# controller_rev1_1_flat.net
KiCad netlist of a schematic drawn in EAGLE
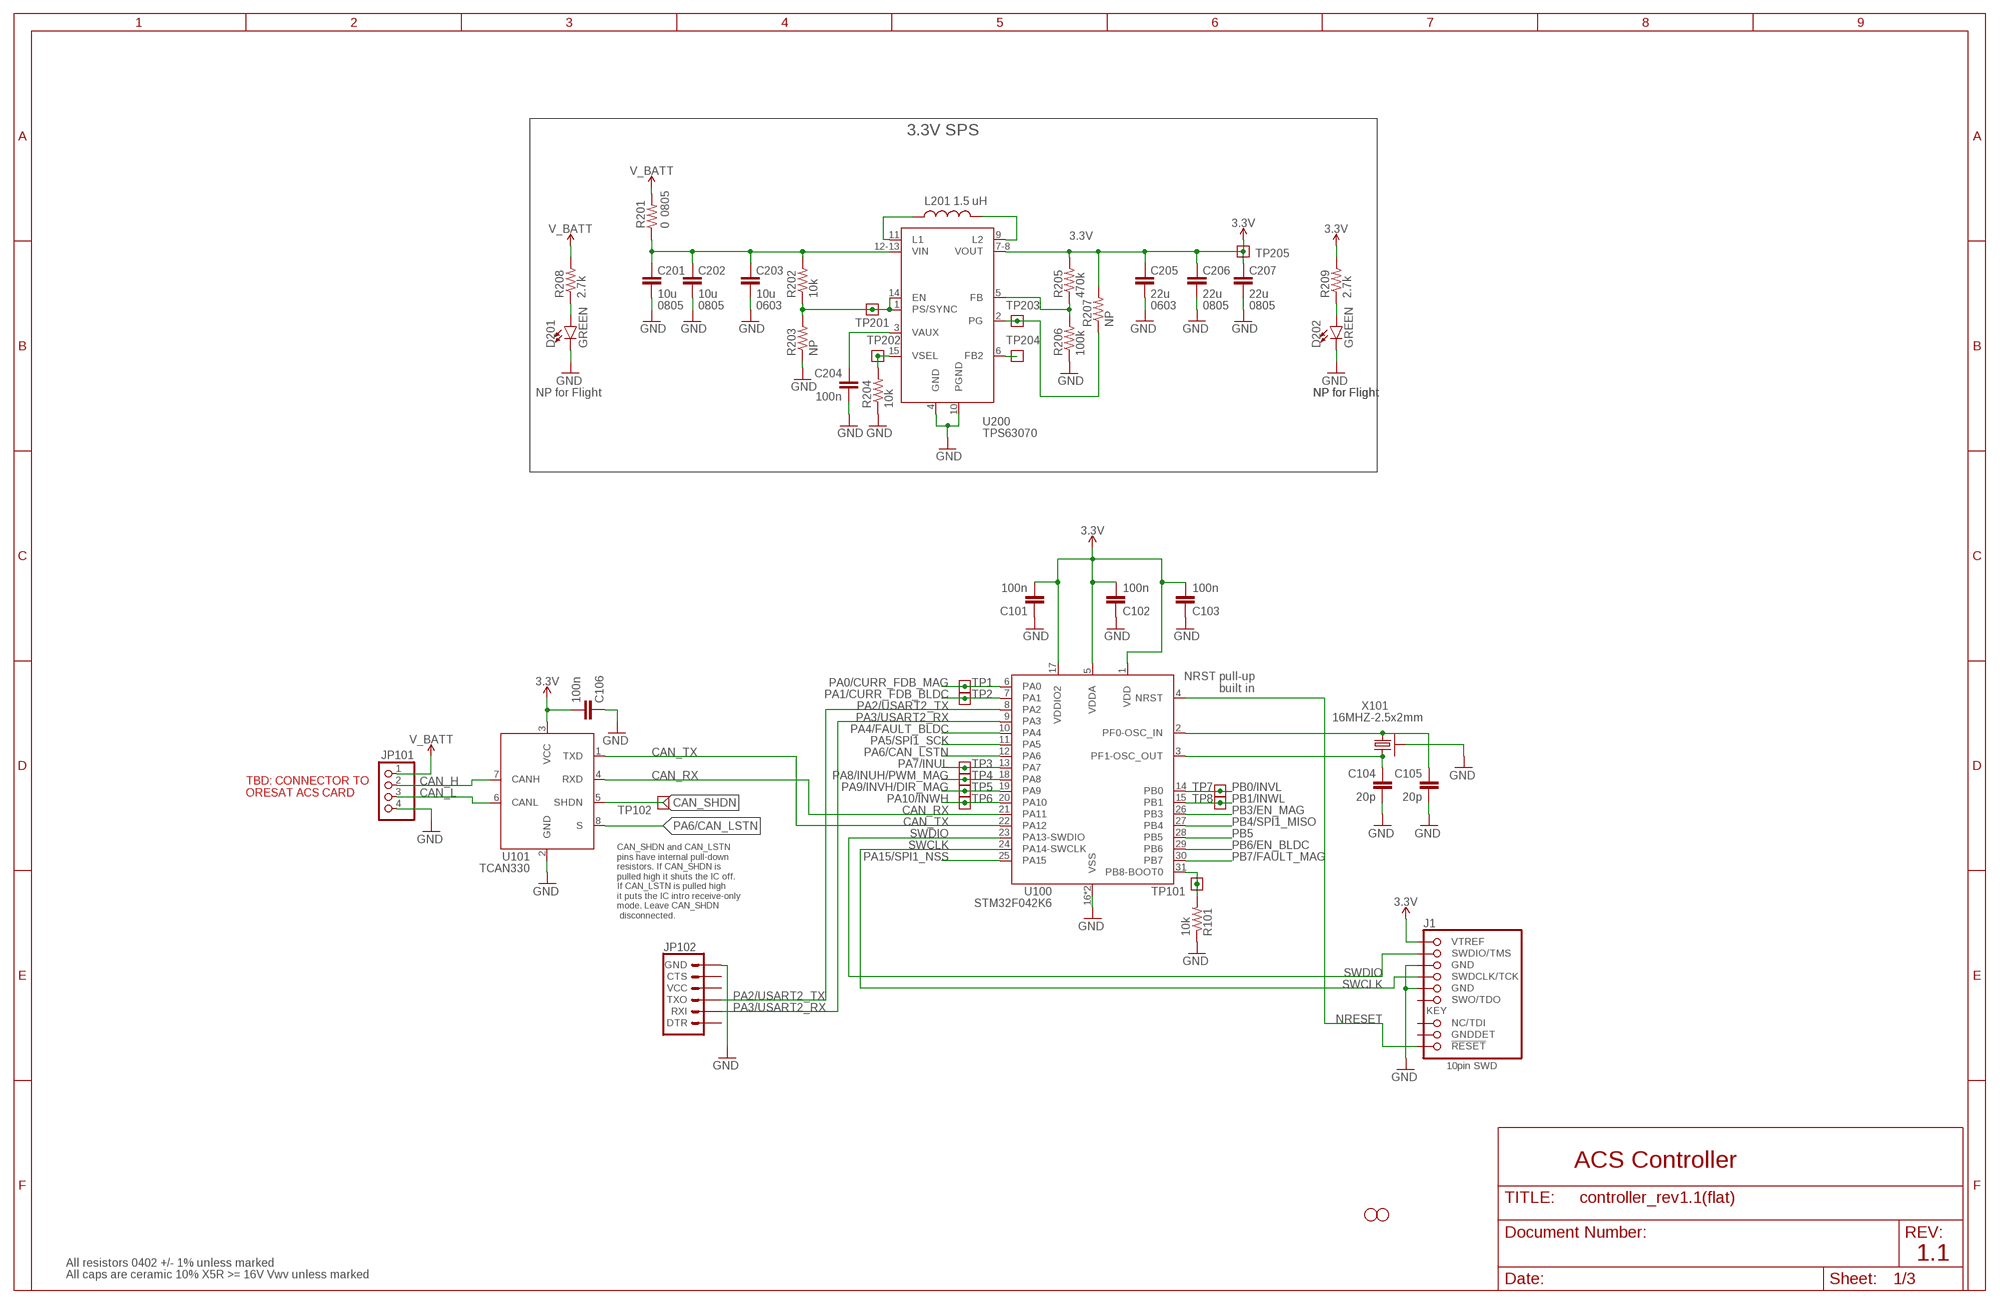
[diagram p0: schematic, sheet 1]
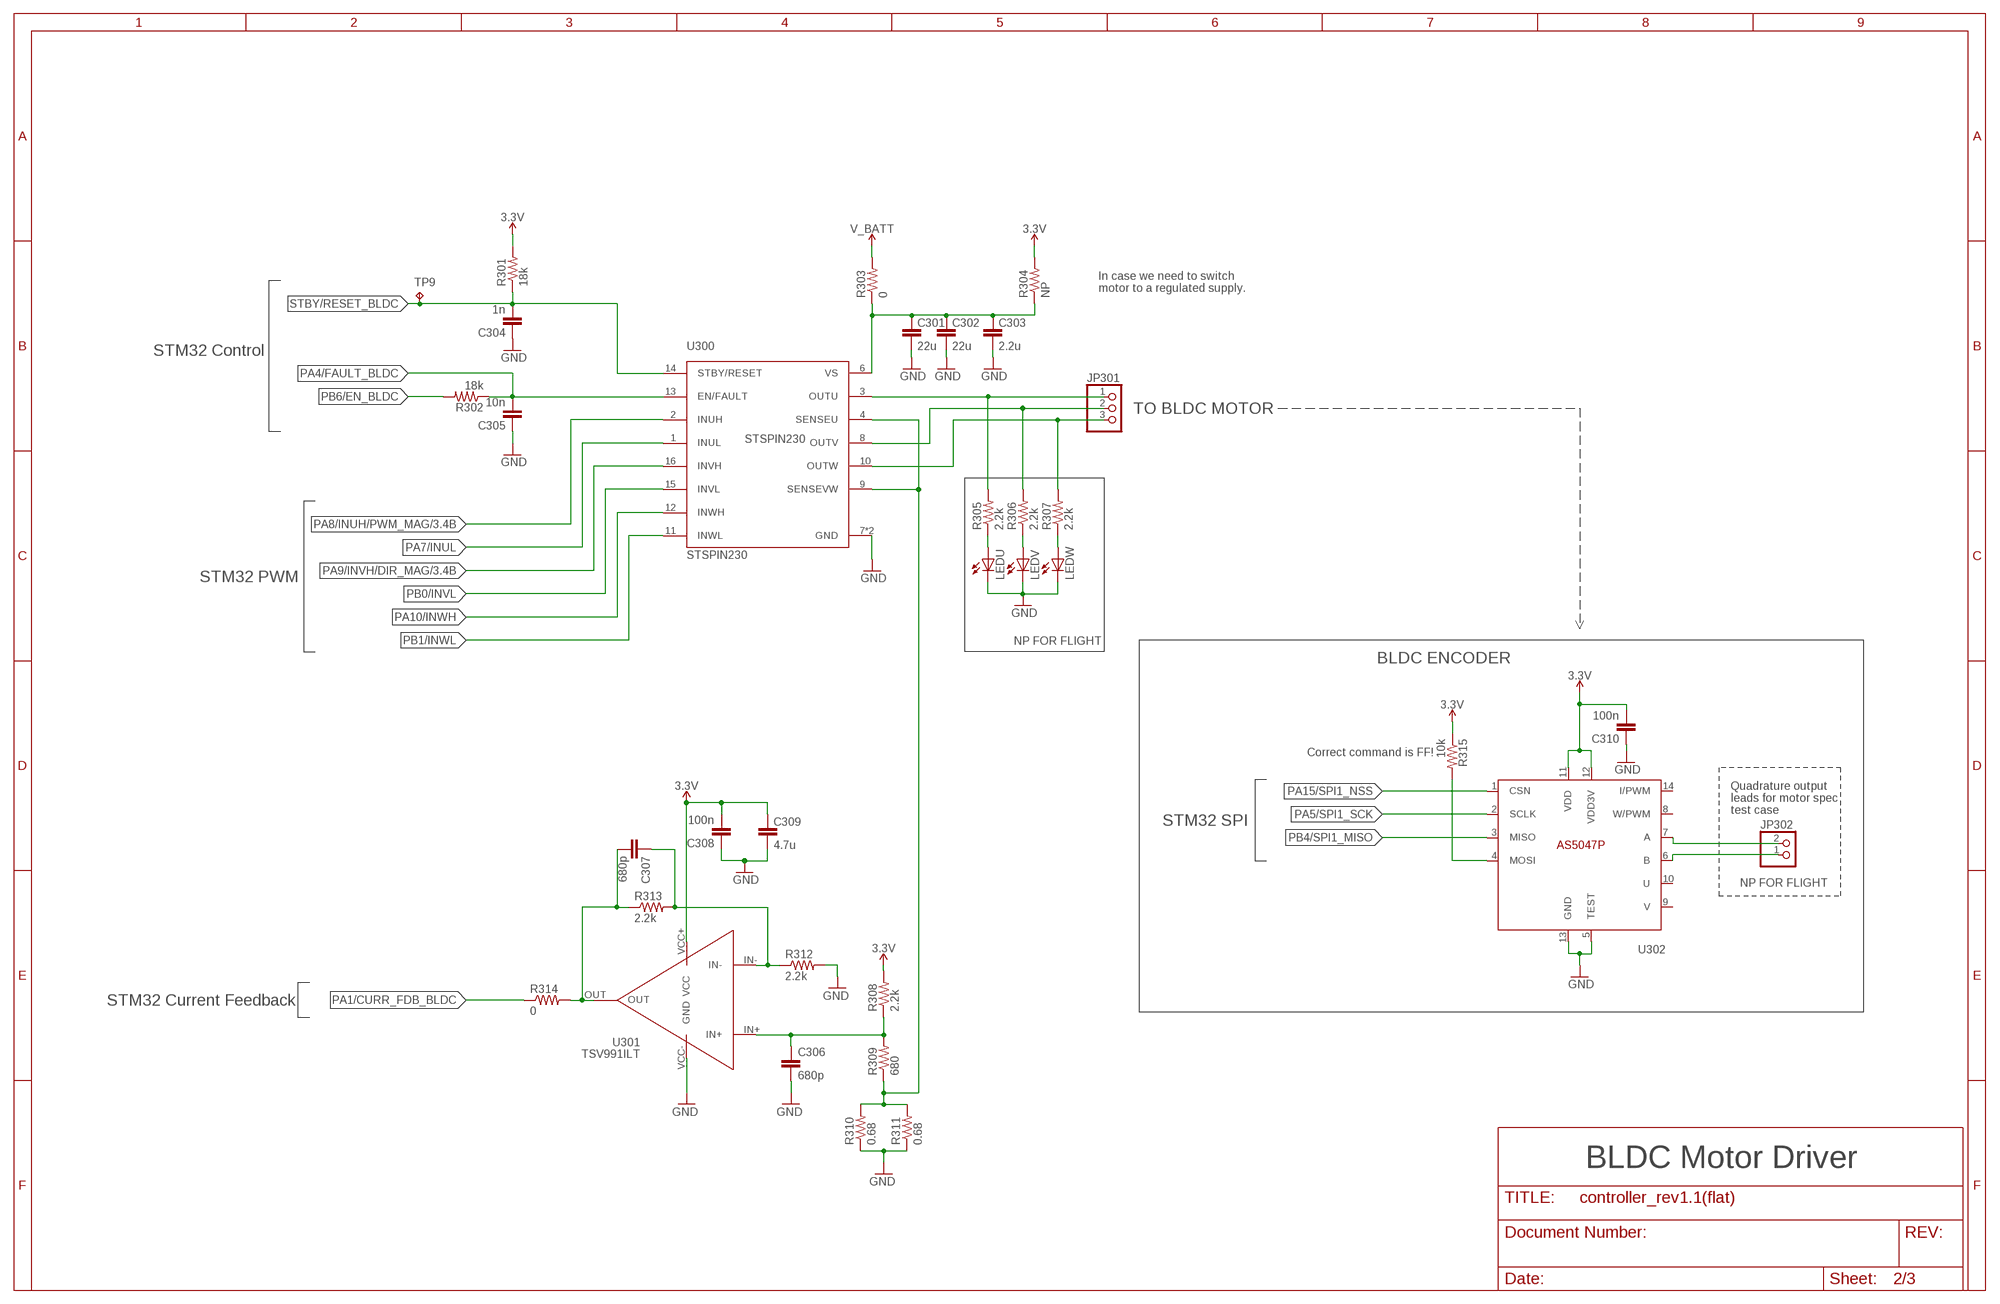
[diagram p1: schematic, sheet 2]
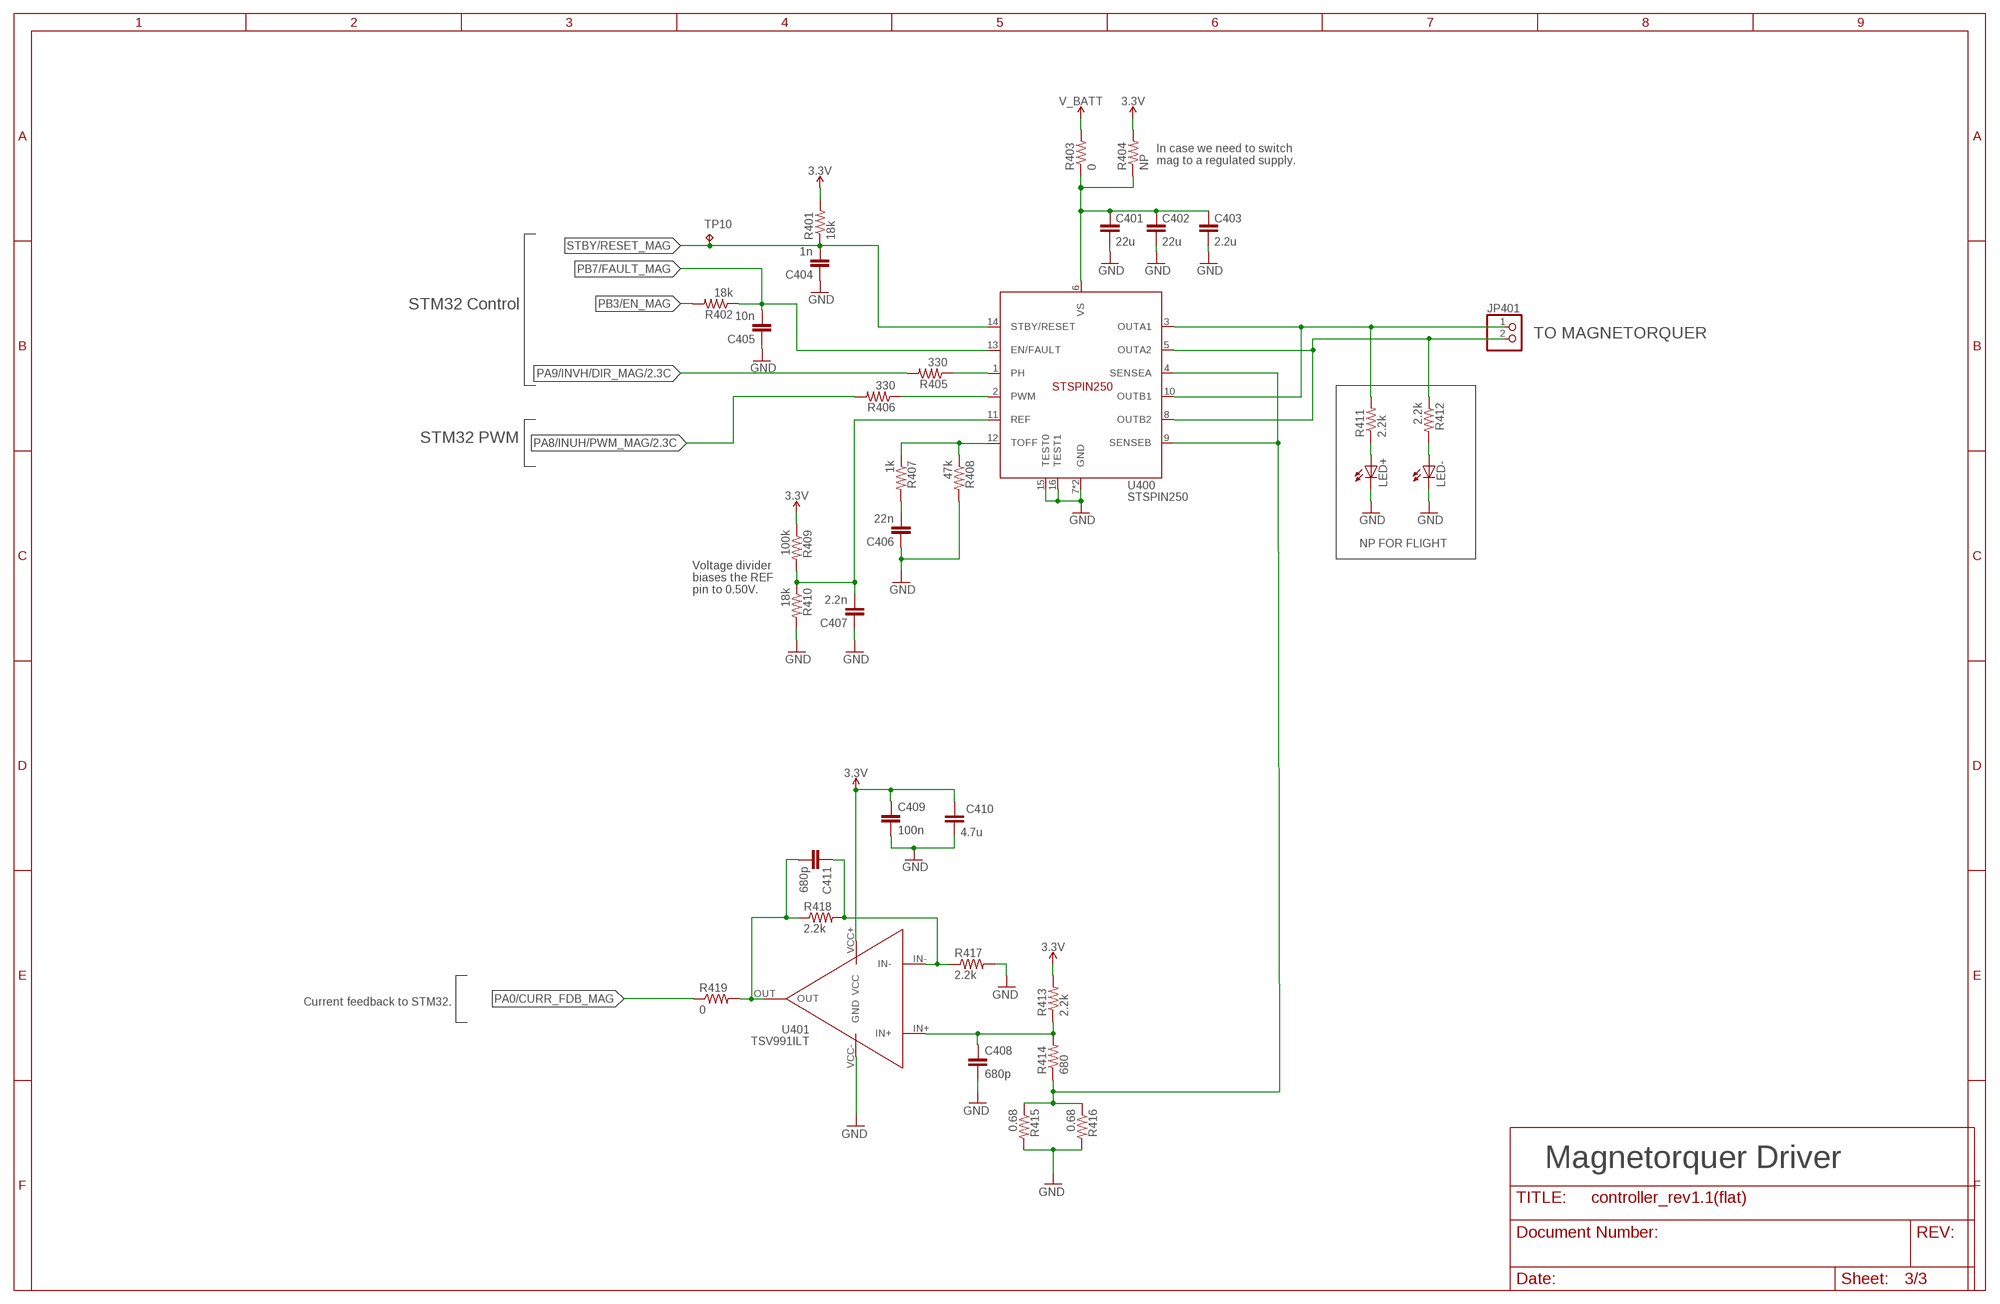
[diagram p2: schematic, sheet 3]

(export (version "E")
  (design (tool "Eeschema 10.0.6"))
  (components
    (comp (ref "C401")
      (value "22u")
      (footprint "eagle-import:.0603-B-NOSILK")
      (fields (field (name "MFR") "Samsung") (field (name "MPN") "CL05B104KO5NNNC"))
      (libsource (lib "eagle-import") (part "C-EU0603-B-NOSILK"))
    )
    (comp (ref "C402")
      (value "22u")
      (footprint "eagle-import:.0603-B-NOSILK")
      (fields (field (name "MFR") "Samsung") (field (name "MPN") "CL05B104KO5NNNC"))
      (libsource (lib "eagle-import") (part "C-EU0603-B-NOSILK"))
    )
    (comp (ref "C403")
      (value "2.2u")
      (footprint "eagle-import:.0603-B-NOSILK")
      (fields (field (name "MFR") "Samsung") (field (name "MPN") "CL05B104KO5NNNC"))
      (libsource (lib "eagle-import") (part "C-EU0603-B-NOSILK"))
    )
    (comp (ref "C404")
      (value "1n")
      (footprint "eagle-import:.0402-B-NOSILK")
      (fields (field (name "MFR") "Samsung") (field (name "MPN") "CL05B104KO5NNNC"))
      (libsource (lib "eagle-import") (part "rcl_custom_C-EU0402-B-NOSILK"))
    )
    (comp (ref "C405")
      (value "10n")
      (footprint "eagle-import:.0402-B-NOSILK")
      (fields (field (name "MFR") "Samsung") (field (name "MPN") "CL05B104KO5NNNC"))
      (libsource (lib "eagle-import") (part "rcl_custom_C-EU0402-B-NOSILK"))
    )
    (comp (ref "C406")
      (value "22n")
      (footprint "eagle-import:.0402-B-NOSILK")
      (fields (field (name "MFR") "Samsung") (field (name "MPN") "CL05B104KO5NNNC"))
      (libsource (lib "eagle-import") (part "rcl_custom_C-EU0402-B-NOSILK"))
    )
    (comp (ref "C407")
      (value "2.2n")
      (footprint "eagle-import:.0402-B-NOSILK")
      (fields (field (name "MFR") "Samsung") (field (name "MPN") "CL05B104KO5NNNC"))
      (libsource (lib "eagle-import") (part "rcl_custom_C-EU0402-B-NOSILK"))
    )
    (comp (ref "C408")
      (value "680p")
      (footprint "eagle-import:.0402-B-NOSILK")
      (fields (field (name "MFR") "Samsung") (field (name "MPN") "CL05B104KO5NNNC"))
      (libsource (lib "eagle-import") (part "rcl_custom_C-EU0402-B-NOSILK"))
    )
    (comp (ref "C409")
      (value "100n")
      (footprint "eagle-import:.0402-B-NOSILK")
      (fields (field (name "MFR") "Samsung") (field (name "MPN") "CL05B104KO5NNNC"))
      (libsource (lib "eagle-import") (part "rcl_custom_C-EU0402-B-NOSILK"))
    )
    (comp (ref "C410")
      (value "4.7u")
      (footprint "eagle-import:.0603-B-NOSILK")
      (fields (field (name "MFR") "Samsung") (field (name "MPN") "CL05B104KO5NNNC"))
      (libsource (lib "eagle-import") (part "C-EU0603-B-NOSILK"))
    )
    (comp (ref "C411")
      (value "680p")
      (footprint "eagle-import:.0402-B-NOSILK")
      (fields (field (name "MFR") "Samsung") (field (name "MPN") "CL05B104KO5NNNC"))
      (libsource (lib "eagle-import") (part "rcl_custom_C-EU0402-B-NOSILK"))
    )
    (comp (ref "JP401")
      (value "PINHD-1X2")
      (footprint "eagle-import:1X02")
      (libsource (lib "eagle-import") (part "PINHD-1X2"))
    )
    (comp (ref "LED+")
      (value "LEDCHIP-LED0603")
      (footprint "eagle-import:CHIP-LED0603")
      (libsource (lib "eagle-import") (part "LEDCHIP-LED0603"))
    )
    (comp (ref "LED-")
      (value "LEDCHIP-LED0603")
      (footprint "eagle-import:CHIP-LED0603")
      (libsource (lib "eagle-import") (part "LEDCHIP-LED0603"))
    )
    (comp (ref "R401")
      (value "18k")
      (footprint "eagle-import:.0402-B-NOSILK")
      (fields (field (name "MFR") "Samsung") (field (name "MPN") "RC1005F6653CS"))
      (libsource (lib "eagle-import") (part "rcl_custom_R-US_0402-B-NOSILK"))
    )
    (comp (ref "R402")
      (value "18k")
      (footprint "eagle-import:.0402-B-NOSILK")
      (fields (field (name "MFR") "Samsung") (field (name "MPN") "RC1005F6653CS"))
      (libsource (lib "eagle-import") (part "rcl_custom_R-US_0402-B-NOSILK"))
    )
    (comp (ref "R403")
      (value "0")
      (footprint "eagle-import:.0805-B-NOSILK")
      (libsource (lib "eagle-import") (part "R-US_0805-B-NOSILK"))
    )
    (comp (ref "R404")
      (value "NP")
      (footprint "eagle-import:.0805-B-NOSILK")
      (libsource (lib "eagle-import") (part "R-US_0805-B-NOSILK"))
    )
    (comp (ref "R405")
      (value "330")
      (footprint "eagle-import:.0402-B-NOSILK")
      (fields (field (name "MFR") "Samsung") (field (name "MPN") "RC1005F6653CS"))
      (libsource (lib "eagle-import") (part "rcl_custom_R-US_0402-B-NOSILK"))
    )
    (comp (ref "R406")
      (value "330")
      (footprint "eagle-import:.0402-B-NOSILK")
      (fields (field (name "MFR") "Samsung") (field (name "MPN") "RC1005F6653CS"))
      (libsource (lib "eagle-import") (part "rcl_custom_R-US_0402-B-NOSILK"))
    )
    (comp (ref "R407")
      (value "1k")
      (footprint "eagle-import:.0402-B-NOSILK")
      (fields (field (name "MFR") "Samsung") (field (name "MPN") "RC1005F6653CS"))
      (libsource (lib "eagle-import") (part "rcl_custom_R-US_0402-B-NOSILK"))
    )
    (comp (ref "R408")
      (value "47k")
      (footprint "eagle-import:.0402-B-NOSILK")
      (fields (field (name "MFR") "Samsung") (field (name "MPN") "RC1005F6653CS"))
      (libsource (lib "eagle-import") (part "rcl_custom_R-US_0402-B-NOSILK"))
    )
    (comp (ref "R409")
      (value "100k")
      (footprint "eagle-import:.0402-B-NOSILK")
      (fields (field (name "MFR") "Samsung") (field (name "MPN") "RC1005F6653CS"))
      (libsource (lib "eagle-import") (part "rcl_custom_R-US_0402-B-NOSILK"))
    )
    (comp (ref "R410")
      (value "18k")
      (footprint "eagle-import:.0402-B-NOSILK")
      (fields (field (name "MFR") "Samsung") (field (name "MPN") "RC1005F6653CS"))
      (libsource (lib "eagle-import") (part "rcl_custom_R-US_0402-B-NOSILK"))
    )
    (comp (ref "R411")
      (value "2.2k")
      (footprint "eagle-import:.0805-B-NOSILK")
      (libsource (lib "eagle-import") (part "R-US_0805-B-NOSILK"))
    )
    (comp (ref "R412")
      (value "2.2k")
      (footprint "eagle-import:.0805-B-NOSILK")
      (libsource (lib "eagle-import") (part "R-US_0805-B-NOSILK"))
    )
    (comp (ref "R413")
      (value "2.2k")
      (footprint "eagle-import:.0402-B-NOSILK")
      (fields (field (name "MFR") "Samsung") (field (name "MPN") "RC1005F6653CS"))
      (libsource (lib "eagle-import") (part "rcl_custom_R-US_0402-B-NOSILK"))
    )
    (comp (ref "R414")
      (value "680")
      (footprint "eagle-import:.0402-B-NOSILK")
      (fields (field (name "MFR") "Samsung") (field (name "MPN") "RC1005F6653CS"))
      (libsource (lib "eagle-import") (part "rcl_custom_R-US_0402-B-NOSILK"))
    )
    (comp (ref "R415")
      (value "0.68")
      (footprint "eagle-import:.0805-B-NOSILK")
      (libsource (lib "eagle-import") (part "R-US_0805-B-NOSILK"))
    )
    (comp (ref "R416")
      (value "0.68")
      (footprint "eagle-import:.0805-B-NOSILK")
      (libsource (lib "eagle-import") (part "R-US_0805-B-NOSILK"))
    )
    (comp (ref "R417")
      (value "2.2k")
      (footprint "eagle-import:.0402-B-NOSILK")
      (fields (field (name "MFR") "Samsung") (field (name "MPN") "RC1005F6653CS"))
      (libsource (lib "eagle-import") (part "rcl_custom_R-US_0402-B-NOSILK"))
    )
    (comp (ref "R418")
      (value "2.2k")
      (footprint "eagle-import:.0402-B-NOSILK")
      (fields (field (name "MFR") "Samsung") (field (name "MPN") "RC1005F6653CS"))
      (libsource (lib "eagle-import") (part "rcl_custom_R-US_0402-B-NOSILK"))
    )
    (comp (ref "R419")
      (value "0")
      (footprint "eagle-import:.0402-B-NOSILK")
      (fields (field (name "MFR") "Samsung") (field (name "MPN") "RC1005F6653CS"))
      (libsource (lib "eagle-import") (part "rcl_custom_R-US_0402-B-NOSILK"))
    )
    (comp (ref "TP10")
      (value "TPPAD1-13")
      (footprint "eagle-import:P1-13")
      (libsource (lib "eagle-import") (part "TPPAD1-13"))
    )
    (comp (ref "U400")
      (value "STSPIN250")
      (footprint "eagle-import:VFQPN")
      (libsource (lib "eagle-import") (part "STSPIN250"))
    )
    (comp (ref "U401")
      (value "TSV991ILT")
      (footprint "eagle-import:SOT23-5")
      (libsource (lib "eagle-import") (part "TSV991ILT"))
    )
    (comp (ref "C301")
      (value "22u")
      (footprint "eagle-import:.0603-B-NOSILK")
      (fields (field (name "MFR") "Samsung") (field (name "MPN") "CL05B104KO5NNNC"))
      (libsource (lib "eagle-import") (part "C-EU0603-B-NOSILK"))
    )
    (comp (ref "C302")
      (value "22u")
      (footprint "eagle-import:.0603-B-NOSILK")
      (fields (field (name "MFR") "Samsung") (field (name "MPN") "CL05B104KO5NNNC"))
      (libsource (lib "eagle-import") (part "C-EU0603-B-NOSILK"))
    )
    (comp (ref "C303")
      (value "2.2u")
      (footprint "eagle-import:.0603-B-NOSILK")
      (fields (field (name "MFR") "Samsung") (field (name "MPN") "CL05B104KO5NNNC"))
      (libsource (lib "eagle-import") (part "C-EU0603-B-NOSILK"))
    )
    (comp (ref "C304")
      (value "1n")
      (footprint "eagle-import:.0402-B-NOSILK")
      (fields (field (name "MFR") "Samsung") (field (name "MPN") "CL05B104KO5NNNC"))
      (libsource (lib "eagle-import") (part "rcl_custom_C-EU0402-B-NOSILK"))
    )
    (comp (ref "C305")
      (value "10n")
      (footprint "eagle-import:.0402-B-NOSILK")
      (fields (field (name "MFR") "Samsung") (field (name "MPN") "CL05B104KO5NNNC"))
      (libsource (lib "eagle-import") (part "rcl_custom_C-EU0402-B-NOSILK"))
    )
    (comp (ref "C306")
      (value "680p")
      (footprint "eagle-import:.0402-B-NOSILK")
      (fields (field (name "MFR") "Samsung") (field (name "MPN") "CL05B104KO5NNNC"))
      (libsource (lib "eagle-import") (part "rcl_custom_C-EU0402-B-NOSILK"))
    )
    (comp (ref "C307")
      (value "680p")
      (footprint "eagle-import:.0402-B-NOSILK")
      (fields (field (name "MFR") "Samsung") (field (name "MPN") "CL05B104KO5NNNC"))
      (libsource (lib "eagle-import") (part "rcl_custom_C-EU0402-B-NOSILK"))
    )
    (comp (ref "C308")
      (value "100n")
      (footprint "eagle-import:.0402-B-NOSILK")
      (fields (field (name "MFR") "Samsung") (field (name "MPN") "CL05B104KO5NNNC"))
      (libsource (lib "eagle-import") (part "rcl_custom_C-EU0402-B-NOSILK"))
    )
    (comp (ref "C309")
      (value "4.7u")
      (footprint "eagle-import:.0603-B-NOSILK")
      (fields (field (name "MFR") "Samsung") (field (name "MPN") "CL05B104KO5NNNC"))
      (libsource (lib "eagle-import") (part "C-EU0603-B-NOSILK"))
    )
    (comp (ref "C310")
      (value "100n")
      (footprint "eagle-import:.0402-B-NOSILK")
      (fields (field (name "MFR") "Samsung") (field (name "MPN") "CL05B104KO5NNNC"))
      (libsource (lib "eagle-import") (part "rcl_custom_C-EU0402-B-NOSILK"))
    )
    (comp (ref "JP301")
      (value "PINHD-1X3")
      (footprint "eagle-import:1X03")
      (libsource (lib "eagle-import") (part "PINHD-1X3"))
    )
    (comp (ref "JP302")
      (value "PINHD-1X2/90")
      (footprint "eagle-import:1X02_90")
      (libsource (lib "eagle-import") (part "PINHD-1X2/90"))
    )
    (comp (ref "LEDU")
      (value "LEDCHIP-LED0603")
      (footprint "eagle-import:CHIP-LED0603")
      (libsource (lib "eagle-import") (part "LEDCHIP-LED0603"))
    )
    (comp (ref "LEDV")
      (value "LEDCHIP-LED0603")
      (footprint "eagle-import:CHIP-LED0603")
      (libsource (lib "eagle-import") (part "LEDCHIP-LED0603"))
    )
    (comp (ref "LEDW")
      (value "LEDCHIP-LED0603")
      (footprint "eagle-import:CHIP-LED0603")
      (libsource (lib "eagle-import") (part "LEDCHIP-LED0603"))
    )
    (comp (ref "R301")
      (value "18k")
      (footprint "eagle-import:.0402-B-NOSILK")
      (fields (field (name "MFR") "Samsung") (field (name "MPN") "RC1005F6653CS"))
      (libsource (lib "eagle-import") (part "rcl_custom_R-US_0402-B-NOSILK"))
    )
    (comp (ref "R302")
      (value "18k")
      (footprint "eagle-import:.0402-B-NOSILK")
      (fields (field (name "MFR") "Samsung") (field (name "MPN") "RC1005F6653CS"))
      (libsource (lib "eagle-import") (part "rcl_custom_R-US_0402-B-NOSILK"))
    )
    (comp (ref "R303")
      (value "0")
      (footprint "eagle-import:.0805-B-NOSILK")
      (libsource (lib "eagle-import") (part "R-US_0805-B-NOSILK"))
    )
    (comp (ref "R304")
      (value "NP")
      (footprint "eagle-import:.0805-B-NOSILK")
      (libsource (lib "eagle-import") (part "R-US_0805-B-NOSILK"))
    )
    (comp (ref "R305")
      (value "2.2k")
      (footprint "eagle-import:.0805-B-NOSILK")
      (libsource (lib "eagle-import") (part "R-US_0805-B-NOSILK"))
    )
    (comp (ref "R306")
      (value "2.2k")
      (footprint "eagle-import:.0805-B-NOSILK")
      (libsource (lib "eagle-import") (part "R-US_0805-B-NOSILK"))
    )
    (comp (ref "R307")
      (value "2.2k")
      (footprint "eagle-import:.0805-B-NOSILK")
      (libsource (lib "eagle-import") (part "R-US_0805-B-NOSILK"))
    )
    (comp (ref "R308")
      (value "2.2k")
      (footprint "eagle-import:.0402-B-NOSILK")
      (fields (field (name "MFR") "Samsung") (field (name "MPN") "RC1005F6653CS"))
      (libsource (lib "eagle-import") (part "rcl_custom_R-US_0402-B-NOSILK"))
    )
    (comp (ref "R309")
      (value "680")
      (footprint "eagle-import:.0402-B-NOSILK")
      (fields (field (name "MFR") "Samsung") (field (name "MPN") "RC1005F6653CS"))
      (libsource (lib "eagle-import") (part "rcl_custom_R-US_0402-B-NOSILK"))
    )
    (comp (ref "R310")
      (value "0.68")
      (footprint "eagle-import:.0805-B-NOSILK")
      (libsource (lib "eagle-import") (part "R-US_0805-B-NOSILK"))
    )
    (comp (ref "R311")
      (value "0.68")
      (footprint "eagle-import:.0805-B-NOSILK")
      (libsource (lib "eagle-import") (part "R-US_0805-B-NOSILK"))
    )
    (comp (ref "R312")
      (value "2.2k")
      (footprint "eagle-import:.0402-B-NOSILK")
      (fields (field (name "MFR") "Samsung") (field (name "MPN") "RC1005F6653CS"))
      (libsource (lib "eagle-import") (part "rcl_custom_R-US_0402-B-NOSILK"))
    )
    (comp (ref "R313")
      (value "2.2k")
      (footprint "eagle-import:.0402-B-NOSILK")
      (fields (field (name "MFR") "Samsung") (field (name "MPN") "RC1005F6653CS"))
      (libsource (lib "eagle-import") (part "rcl_custom_R-US_0402-B-NOSILK"))
    )
    (comp (ref "R314")
      (value "0")
      (footprint "eagle-import:.0402-B-NOSILK")
      (fields (field (name "MFR") "Samsung") (field (name "MPN") "RC1005F6653CS"))
      (libsource (lib "eagle-import") (part "rcl_custom_R-US_0402-B-NOSILK"))
    )
    (comp (ref "R315")
      (value "10k")
      (footprint "eagle-import:.0402-B-NOSILK")
      (fields (field (name "MFR") "Samsung") (field (name "MPN") "RC1005F6653CS"))
      (libsource (lib "eagle-import") (part "rcl_custom_R-US_0402-B-NOSILK"))
    )
    (comp (ref "TP9")
      (value "TPPAD1-13")
      (footprint "eagle-import:P1-13")
      (libsource (lib "eagle-import") (part "TPPAD1-13"))
    )
    (comp (ref "U300")
      (value "STSPIN230")
      (footprint "eagle-import:VFQFPN")
      (libsource (lib "eagle-import") (part "STSPIN230"))
    )
    (comp (ref "U301")
      (value "TSV991ILT")
      (footprint "eagle-import:SOT23-5")
      (libsource (lib "eagle-import") (part "TSV991ILT"))
    )
    (comp (ref "U302")
      (value "AS5047P")
      (footprint "eagle-import:TSSOP14")
      (libsource (lib "eagle-import") (part "AS5047P"))
    )
    (comp (ref "C101")
      (value "100n")
      (footprint "eagle-import:.0402-B-NOSILK")
      (fields (field (name "MFR") "Samsung") (field (name "MPN") "CL05B104KO5NNNC"))
      (libsource (lib "eagle-import") (part "rcl_custom_C-EU0402-B-NOSILK"))
    )
    (comp (ref "C102")
      (value "100n")
      (footprint "eagle-import:.0402-B-NOSILK")
      (fields (field (name "MFR") "Samsung") (field (name "MPN") "CL05B104KO5NNNC"))
      (libsource (lib "eagle-import") (part "rcl_custom_C-EU0402-B-NOSILK"))
    )
    (comp (ref "C103")
      (value "100n")
      (footprint "eagle-import:.0402-B-NOSILK")
      (fields (field (name "MFR") "Samsung") (field (name "MPN") "CL05B104KO5NNNC"))
      (libsource (lib "eagle-import") (part "rcl_custom_C-EU0402-B-NOSILK"))
    )
    (comp (ref "C104")
      (value "20p")
      (footprint "eagle-import:.0402-B-NOSILK")
      (fields (field (name "MFR") "Samsung") (field (name "MPN") "CL05C200JB51PNC"))
      (libsource (lib "eagle-import") (part "rcl_custom_C-EU0402-B-NOSILK"))
    )
    (comp (ref "C105")
      (value "20p")
      (footprint "eagle-import:.0402-B-NOSILK")
      (fields (field (name "MFR") "Samsung") (field (name "MPN") "CL05C200JB51PNC"))
      (libsource (lib "eagle-import") (part "rcl_custom_C-EU0402-B-NOSILK"))
    )
    (comp (ref "C106")
      (value "100n")
      (footprint "eagle-import:.0402-B-NOSILK")
      (fields (field (name "MFR") "Samsung") (field (name "MPN") "CL05B104KO5NNNC"))
      (libsource (lib "eagle-import") (part "rcl_custom_C-EU0402-B-NOSILK"))
    )
    (comp (ref "C201")
      (value "10u")
      (footprint "eagle-import:.0805-B-NOSILK")
      (libsource (lib "eagle-import") (part "C-EU0805-B-NOSILK"))
    )
    (comp (ref "C202")
      (value "10u")
      (footprint "eagle-import:.0805-B-NOSILK")
      (libsource (lib "eagle-import") (part "C-EU0805-B-NOSILK"))
    )
    (comp (ref "C203")
      (value "10u")
      (footprint "eagle-import:.0603-B-NOSILK")
      (fields (field (name "MFR") "Samsung") (field (name "MPN") "CL05B104KO5NNNC"))
      (libsource (lib "eagle-import") (part "C-EU0603-B-NOSILK"))
    )
    (comp (ref "C204")
      (value "100n")
      (footprint "eagle-import:.0402-B-NOSILK")
      (fields (field (name "MFR") "Samsung") (field (name "MPN") "CL05B104KO5NNNC"))
      (libsource (lib "eagle-import") (part "rcl_custom_C-EU0402-B-NOSILK"))
    )
    (comp (ref "C205")
      (value "22u")
      (footprint "eagle-import:.0603-B-NOSILK")
      (fields (field (name "MFR") "Samsung") (field (name "MPN") "CL05B104KO5NNNC"))
      (libsource (lib "eagle-import") (part "C-EU0603-B-NOSILK"))
    )
    (comp (ref "C206")
      (value "22u")
      (footprint "eagle-import:.0805-B-NOSILK")
      (libsource (lib "eagle-import") (part "C-EU0805-B-NOSILK"))
    )
    (comp (ref "C207")
      (value "22u")
      (footprint "eagle-import:.0805-B-NOSILK")
      (libsource (lib "eagle-import") (part "C-EU0805-B-NOSILK"))
    )
    (comp (ref "D201")
      (value "GREEN")
      (footprint "eagle-import:LED-0603")
      (libsource (lib "eagle-import") (part "LED-GREEN0603"))
    )
    (comp (ref "D202")
      (value "GREEN")
      (footprint "eagle-import:LED-0603")
      (libsource (lib "eagle-import") (part "LED-GREEN0603"))
    )
    (comp (ref "H1")
      (value "STAND-OFFTIGHT")
      (footprint "eagle-import:STAND-OFF-TIGHT")
      (libsource (lib "eagle-import") (part "STAND-OFFTIGHT"))
    )
    (comp (ref "H2")
      (value "STAND-OFFTIGHT")
      (footprint "eagle-import:STAND-OFF-TIGHT")
      (libsource (lib "eagle-import") (part "STAND-OFFTIGHT"))
    )
    (comp (ref "J1")
      (value "1.27MM-SWD-CONNECTOR")
      (footprint "eagle-import:1.27MM_2X5")
      (libsource (lib "eagle-import") (part "1.27MM-SWD-CONNECTOR"))
    )
    (comp (ref "JP101")
      (value "PINHD-1X4")
      (footprint "eagle-import:1X04")
      (libsource (lib "eagle-import") (part "PINHD-1X4"))
    )
    (comp (ref "JP102")
      (value "6_PIN_SERIAL_TARGETSILK")
      (footprint "eagle-import:6_PIN_SERIAL_TARGET_SIDE_W_SILK")
      (libsource (lib "eagle-import") (part "6_PIN_SERIAL_TARGETSILK"))
    )
    (comp (ref "L201")
      (value "1.5 uH")
      (footprint "eagle-import:L-COILCRAFT-XFL4020")
      (fields (field (name "MFR") "Coilcraft") (field (name "MPN") "XFL4020-152ME"))
      (libsource (lib "eagle-import") (part "L-COILCRAFT-XFL4020"))
    )
    (comp (ref "R101")
      (value "10k")
      (footprint "eagle-import:.0402-B-NOSILK")
      (fields (field (name "MFR") "Samsung") (field (name "MPN") "RC1005F6653CS"))
      (libsource (lib "eagle-import") (part "rcl_custom_R-US_0402-B-NOSILK"))
    )
    (comp (ref "R201")
      (value "0")
      (footprint "eagle-import:.0805-B-NOSILK")
      (fields (field (name "MFR") "Rohm") (field (name "MPN") "MCR10EZPJ000"))
      (libsource (lib "eagle-import") (part "rcl_custom_R-US_0805-B-NOSILK"))
    )
    (comp (ref "R202")
      (value "10k")
      (footprint "eagle-import:.0402-B-NOSILK")
      (fields (field (name "MFR") "Samsung") (field (name "MPN") "RC1005F6653CS"))
      (libsource (lib "eagle-import") (part "rcl_custom_R-US_0402-B-NOSILK"))
    )
    (comp (ref "R203")
      (value "NP")
      (footprint "eagle-import:.0402-B-NOSILK")
      (fields (field (name "MFR") "Samsung") (field (name "MPN") "RC1005F6653CS"))
      (libsource (lib "eagle-import") (part "rcl_custom_R-US_0402-B-NOSILK"))
    )
    (comp (ref "R204")
      (value "10k")
      (footprint "eagle-import:.0402-B-NOSILK")
      (fields (field (name "MFR") "Samsung") (field (name "MPN") "RC1005F6653CS"))
      (libsource (lib "eagle-import") (part "rcl_custom_R-US_0402-B-NOSILK"))
    )
    (comp (ref "R205")
      (value "470k")
      (footprint "eagle-import:.0402-B-NOSILK")
      (fields (field (name "MFR") "Samsung") (field (name "MPN") "RC1005F6653CS"))
      (libsource (lib "eagle-import") (part "rcl_custom_R-US_0402-B-NOSILK"))
    )
    (comp (ref "R206")
      (value "100k")
      (footprint "eagle-import:.0402-B-NOSILK")
      (fields (field (name "MFR") "Samsung") (field (name "MPN") "RC1005F6653CS"))
      (libsource (lib "eagle-import") (part "rcl_custom_R-US_0402-B-NOSILK"))
    )
    (comp (ref "R207")
      (value "NP")
      (footprint "eagle-import:.0402-B-NOSILK")
      (fields (field (name "MFR") "Samsung") (field (name "MPN") "RC1005F6653CS"))
      (libsource (lib "eagle-import") (part "rcl_custom_R-US_0402-B-NOSILK"))
    )
    (comp (ref "R208")
      (value "2.7k")
      (footprint "eagle-import:.0402-B-NOSILK")
      (fields (field (name "MFR") "Samsung") (field (name "MPN") "RC1005F6653CS"))
      (libsource (lib "eagle-import") (part "rcl_custom_R-US_0402-B-NOSILK"))
    )
    (comp (ref "R209")
      (value "2.7k")
      (footprint "eagle-import:.0402-B-NOSILK")
      (fields (field (name "MFR") "Samsung") (field (name "MPN") "RC1005F6653CS"))
      (libsource (lib "eagle-import") (part "rcl_custom_R-US_0402-B-NOSILK"))
    )
    (comp (ref "TP1")
      (value "TEST-POINT")
      (footprint "eagle-import:2MM-TEST-POINT")
      (libsource (lib "eagle-import") (part "TEST-POINT"))
    )
    (comp (ref "TP2")
      (value "TEST-POINT")
      (footprint "eagle-import:2MM-TEST-POINT")
      (libsource (lib "eagle-import") (part "TEST-POINT"))
    )
    (comp (ref "TP3")
      (value "TEST-POINT")
      (footprint "eagle-import:2MM-TEST-POINT")
      (libsource (lib "eagle-import") (part "TEST-POINT"))
    )
    (comp (ref "TP4")
      (value "TEST-POINT")
      (footprint "eagle-import:2MM-TEST-POINT")
      (libsource (lib "eagle-import") (part "TEST-POINT"))
    )
    (comp (ref "TP5")
      (value "TEST-POINT")
      (footprint "eagle-import:2MM-TEST-POINT")
      (libsource (lib "eagle-import") (part "TEST-POINT"))
    )
    (comp (ref "TP6")
      (value "TEST-POINT")
      (footprint "eagle-import:2MM-TEST-POINT")
      (libsource (lib "eagle-import") (part "TEST-POINT"))
    )
    (comp (ref "TP7")
      (value "TEST-POINT")
      (footprint "eagle-import:2MM-TEST-POINT")
      (libsource (lib "eagle-import") (part "TEST-POINT"))
    )
    (comp (ref "TP8")
      (value "TEST-POINT")
      (footprint "eagle-import:2MM-TEST-POINT")
      (libsource (lib "eagle-import") (part "TEST-POINT"))
    )
    (comp (ref "TP101")
      (value "TEST-POINT")
      (footprint "eagle-import:2MM-TEST-POINT")
      (libsource (lib "eagle-import") (part "TEST-POINT"))
    )
    (comp (ref "TP102")
      (value "TEST-POINT")
      (footprint "eagle-import:2MM-TEST-POINT")
      (libsource (lib "eagle-import") (part "TEST-POINT"))
    )
    (comp (ref "TP201")
      (value "TEST-POINT")
      (footprint "eagle-import:2MM-TEST-POINT")
      (libsource (lib "eagle-import") (part "TEST-POINT"))
    )
    (comp (ref "TP202")
      (value "TEST-POINT")
      (footprint "eagle-import:2MM-TEST-POINT")
      (libsource (lib "eagle-import") (part "TEST-POINT"))
    )
    (comp (ref "TP203")
      (value "TEST-POINT")
      (footprint "eagle-import:2MM-TEST-POINT")
      (libsource (lib "eagle-import") (part "TEST-POINT"))
    )
    (comp (ref "TP204")
      (value "TEST-POINT")
      (footprint "eagle-import:2MM-TEST-POINT")
      (libsource (lib "eagle-import") (part "TEST-POINT"))
    )
    (comp (ref "TP205")
      (value "TEST-POINT")
      (footprint "eagle-import:2MM-TEST-POINT")
      (libsource (lib "eagle-import") (part "TEST-POINT"))
    )
    (comp (ref "U100")
      (value "STM32F042K6")
      (footprint "eagle-import:QFP32-7X7")
      (fields (field (name "MFR") "STMicroelectronics") (field (name "MPN") "STM32F042K6T7"))
      (libsource (lib "eagle-import") (part "STM32F042K6"))
    )
    (comp (ref "U101")
      (value "TCAN330")
      (footprint "eagle-import:SOT23-8_TI-DCN")
      (fields (field (name "MFR") "Texas Instruments") (field (name "MPN") "TCAN330GDCNT"))
      (libsource (lib "eagle-import") (part "TCAN330"))
    )
    (comp (ref "U200")
      (value "TPS63070")
      (footprint "eagle-import:TPS63070X")
      (libsource (lib "eagle-import") (part "TPS63070X"))
    )
    (comp (ref "X101")
      (value "16MHZ-2.5x2mm")
      (footprint "eagle-import:CRYSTAL_2.5X2")
      (fields (field (name "MFR") "ECS Inc.") (field (name "MPN") "ECS-160-10-36Q-ES-TR"))
      (libsource (lib "eagle-import") (part "CRYSTAL-WITH-GND"))
    )
  )
  (nets
    (net (code "1") (name "3.3V") (class "Default")
      (node (ref "C101") (pin "2") (pinfunction "2_2") (pintype "passive"))
      (node (ref "C102") (pin "2") (pinfunction "2_2") (pintype "passive"))
      (node (ref "C103") (pin "2") (pinfunction "2_2") (pintype "passive"))
      (node (ref "C106") (pin "2") (pinfunction "2_2") (pintype "passive"))
      (node (ref "C205") (pin "1") (pinfunction "1_1") (pintype "passive"))
      (node (ref "C206") (pin "1") (pinfunction "1_1") (pintype "passive"))
      (node (ref "C207") (pin "1") (pinfunction "1_1") (pintype "passive"))
      (node (ref "C308") (pin "2") (pinfunction "2_2") (pintype "passive"))
      (node (ref "C309") (pin "1") (pinfunction "1_1") (pintype "passive"))
      (node (ref "C310") (pin "2") (pinfunction "2_2") (pintype "passive"))
      (node (ref "C409") (pin "1") (pinfunction "1_1") (pintype "passive"))
      (node (ref "C410") (pin "1") (pinfunction "1_1") (pintype "passive"))
      (node (ref "J1") (pin "VTREF") (pinfunction "VTREF_VTREF") (pintype "passive"))
      (node (ref "R205") (pin "2") (pinfunction "2_2") (pintype "passive"))
      (node (ref "R207") (pin "2") (pinfunction "2_2") (pintype "passive"))
      (node (ref "R209") (pin "2") (pinfunction "2_2") (pintype "passive"))
      (node (ref "R301") (pin "2") (pinfunction "2_2") (pintype "passive"))
      (node (ref "R304") (pin "2") (pinfunction "2_2") (pintype "passive"))
      (node (ref "R308") (pin "2") (pinfunction "2_2") (pintype "passive"))
      (node (ref "R315") (pin "1") (pinfunction "1_1") (pintype "passive"))
      (node (ref "R401") (pin "2") (pinfunction "2_2") (pintype "passive"))
      (node (ref "R404") (pin "2") (pinfunction "2_2") (pintype "passive"))
      (node (ref "R409") (pin "1") (pinfunction "1_1") (pintype "passive"))
      (node (ref "R413") (pin "2") (pinfunction "2_2") (pintype "passive"))
      (node (ref "TP205") (pin "1") (pinfunction "1_1") (pintype "passive"))
      (node (ref "U100") (pin "1") (pinfunction "VDD_1") (pintype "power_in"))
      (node (ref "U100") (pin "17") (pinfunction "VDDIO2_17") (pintype "power_in"))
      (node (ref "U100") (pin "5") (pinfunction "VDDA_5") (pintype "power_in"))
      (node (ref "U101") (pin "3") (pinfunction "VCC_3") (pintype "power_in"))
      (node (ref "U200") (pin "7-8") (pinfunction "VOUT_7-8") (pintype "power_in"))
      (node (ref "U301") (pin "VCC+") (pinfunction "VCC_VCC+") (pintype "bidirectional"))
      (node (ref "U302") (pin "11") (pinfunction "VDD_11") (pintype "power_in"))
      (node (ref "U302") (pin "12") (pinfunction "VDD3V_12") (pintype "power_in"))
      (node (ref "U401") (pin "VCC+") (pinfunction "VCC_VCC+") (pintype "bidirectional"))
    )
    (net (code "2") (name "CAN_H") (class "Default")
      (node (ref "JP101") (pin "2") (pinfunction "2_2") (pintype "passive"))
      (node (ref "U101") (pin "7") (pinfunction "CANH_7") (pintype "bidirectional"))
    )
    (net (code "3") (name "CAN_L") (class "Default")
      (node (ref "JP101") (pin "3") (pinfunction "3_3") (pintype "passive"))
      (node (ref "U101") (pin "6") (pinfunction "CANL_6") (pintype "bidirectional"))
    )
    (net (code "4") (name "CAN_RX") (class "Default")
      (node (ref "U100") (pin "21") (pinfunction "PA11_21") (pintype "bidirectional"))
      (node (ref "U101") (pin "4") (pinfunction "RXD_4") (pintype "output"))
    )
    (net (code "5") (name "CAN_SHDN") (class "Default")
      (node (ref "TP102") (pin "1") (pinfunction "1_1") (pintype "passive"))
      (node (ref "U101") (pin "5") (pinfunction "SHDN_5") (pintype "input"))
    )
    (net (code "6") (name "CAN_TX") (class "Default")
      (node (ref "U100") (pin "22") (pinfunction "PA12_22") (pintype "bidirectional"))
      (node (ref "U101") (pin "1") (pinfunction "TXD_1") (pintype "input"))
    )
    (net (code "7") (name "GND") (class "Default")
      (node (ref "C101") (pin "1") (pinfunction "1_1") (pintype "passive"))
      (node (ref "C102") (pin "1") (pinfunction "1_1") (pintype "passive"))
      (node (ref "C103") (pin "1") (pinfunction "1_1") (pintype "passive"))
      (node (ref "C104") (pin "2") (pinfunction "2_2") (pintype "passive"))
      (node (ref "C105") (pin "2") (pinfunction "2_2") (pintype "passive"))
      (node (ref "C106") (pin "1") (pinfunction "1_1") (pintype "passive"))
      (node (ref "C201") (pin "2") (pinfunction "2_2") (pintype "passive"))
      (node (ref "C202") (pin "2") (pinfunction "2_2") (pintype "passive"))
      (node (ref "C203") (pin "2") (pinfunction "2_2") (pintype "passive"))
      (node (ref "C204") (pin "2") (pinfunction "2_2") (pintype "passive"))
      (node (ref "C205") (pin "2") (pinfunction "2_2") (pintype "passive"))
      (node (ref "C206") (pin "2") (pinfunction "2_2") (pintype "passive"))
      (node (ref "C207") (pin "2") (pinfunction "2_2") (pintype "passive"))
      (node (ref "C301") (pin "2") (pinfunction "2_2") (pintype "passive"))
      (node (ref "C302") (pin "2") (pinfunction "2_2") (pintype "passive"))
      (node (ref "C303") (pin "2") (pinfunction "2_2") (pintype "passive"))
      (node (ref "C304") (pin "1") (pinfunction "1_1") (pintype "passive"))
      (node (ref "C305") (pin "1") (pinfunction "1_1") (pintype "passive"))
      (node (ref "C306") (pin "2") (pinfunction "2_2") (pintype "passive"))
      (node (ref "C308") (pin "1") (pinfunction "1_1") (pintype "passive"))
      (node (ref "C309") (pin "2") (pinfunction "2_2") (pintype "passive"))
      (node (ref "C310") (pin "1") (pinfunction "1_1") (pintype "passive"))
      (node (ref "C401") (pin "2") (pinfunction "2_2") (pintype "passive"))
      (node (ref "C402") (pin "2") (pinfunction "2_2") (pintype "passive"))
      (node (ref "C403") (pin "2") (pinfunction "2_2") (pintype "passive"))
      (node (ref "C404") (pin "1") (pinfunction "1_1") (pintype "passive"))
      (node (ref "C405") (pin "1") (pinfunction "1_1") (pintype "passive"))
      (node (ref "C406") (pin "1") (pinfunction "1_1") (pintype "passive"))
      (node (ref "C407") (pin "1") (pinfunction "1_1") (pintype "passive"))
      (node (ref "C408") (pin "2") (pinfunction "2_2") (pintype "passive"))
      (node (ref "C409") (pin "2") (pinfunction "2_2") (pintype "passive"))
      (node (ref "C410") (pin "2") (pinfunction "2_2") (pintype "passive"))
      (node (ref "D201") (pin "C") (pinfunction "C_C") (pintype "passive"))
      (node (ref "D202") (pin "C") (pinfunction "C_C") (pintype "passive"))
      (node (ref "J1") (pin "GND") (pinfunction "GND_GND") (pintype "passive"))
      (node (ref "J1") (pin "GND@2") (pinfunction "GND_GND@2") (pintype "passive"))
      (node (ref "JP101") (pin "4") (pinfunction "4_4") (pintype "passive"))
      (node (ref "JP102") (pin "P$6") (pinfunction "GND_P$6") (pintype "passive"))
      (node (ref "LED+") (pin "C") (pinfunction "C_C") (pintype "passive"))
      (node (ref "LED-") (pin "C") (pinfunction "C_C") (pintype "passive"))
      (node (ref "LEDU") (pin "C") (pinfunction "C_C") (pintype "passive"))
      (node (ref "LEDV") (pin "C") (pinfunction "C_C") (pintype "passive"))
      (node (ref "LEDW") (pin "C") (pinfunction "C_C") (pintype "passive"))
      (node (ref "R101") (pin "1") (pinfunction "1_1") (pintype "passive"))
      (node (ref "R203") (pin "1") (pinfunction "1_1") (pintype "passive"))
      (node (ref "R204") (pin "1") (pinfunction "1_1") (pintype "passive"))
      (node (ref "R206") (pin "1") (pinfunction "1_1") (pintype "passive"))
      (node (ref "R310") (pin "1") (pinfunction "1_1") (pintype "passive"))
      (node (ref "R311") (pin "1") (pinfunction "1_1") (pintype "passive"))
      (node (ref "R312") (pin "2") (pinfunction "2_2") (pintype "passive"))
      (node (ref "R408") (pin "2") (pinfunction "2_2") (pintype "passive"))
      (node (ref "R410") (pin "2") (pinfunction "2_2") (pintype "passive"))
      (node (ref "R415") (pin "2") (pinfunction "2_2") (pintype "passive"))
      (node (ref "R416") (pin "2") (pinfunction "2_2") (pintype "passive"))
      (node (ref "R417") (pin "2") (pinfunction "2_2") (pintype "passive"))
      (node (ref "U100") (pin "16") (pinfunction "VSS_16") (pintype "power_in"))
      (node (ref "U100") (pin "32") (pinfunction "VSS_32") (pintype "power_in"))
      (node (ref "U101") (pin "2") (pinfunction "GND_2") (pintype "power_in"))
      (node (ref "U200") (pin "10") (pinfunction "PGND_10") (pintype "power_in"))
      (node (ref "U200") (pin "4") (pinfunction "GND_4") (pintype "power_in"))
      (node (ref "U300") (pin "7") (pinfunction "GND_7") (pintype "power_in"))
      (node (ref "U300") (pin "EPAD") (pinfunction "GND_EPAD") (pintype "power_in"))
      (node (ref "U301") (pin "VCC-") (pinfunction "GND_VCC-") (pintype "bidirectional"))
      (node (ref "U302") (pin "13") (pinfunction "GND_13") (pintype "power_in"))
      (node (ref "U302") (pin "5") (pinfunction "TEST_5") (pintype "power_in"))
      (node (ref "U400") (pin "15") (pinfunction "TEST0_15") (pintype "bidirectional"))
      (node (ref "U400") (pin "16") (pinfunction "TEST1_16") (pintype "bidirectional"))
      (node (ref "U400") (pin "7") (pinfunction "GND_7") (pintype "power_in"))
      (node (ref "U400") (pin "EPAD") (pinfunction "GND_EPAD") (pintype "power_in"))
      (node (ref "U401") (pin "VCC-") (pinfunction "GND_VCC-") (pintype "bidirectional"))
      (node (ref "X101") (pin "2") (pinfunction "SHIELD_2") (pintype "power_in"))
      (node (ref "X101") (pin "4") (pinfunction "SHIELD_4") (pintype "power_in"))
    )
    (net (code "8") (name "NRESET") (class "Default")
      (node (ref "J1") (pin "!RESET") (pinfunction "~{RESET}_!RESET") (pintype "passive"))
      (node (ref "U100") (pin "4") (pinfunction "NRST_4") (pintype "bidirectional"))
    )
    (net (code "9") (name "Net-(C306-Pad1)") (class "Default")
      (node (ref "C306") (pin "1") (pinfunction "1_1") (pintype "passive"))
      (node (ref "R308") (pin "1") (pinfunction "1_1") (pintype "passive"))
      (node (ref "R309") (pin "2") (pinfunction "2_2") (pintype "passive"))
      (node (ref "U301") (pin "IN+") (pinfunction "IN+_IN+") (pintype "bidirectional"))
    )
    (net (code "10") (name "Net-(C307-Pad1)") (class "Default")
      (node (ref "C307") (pin "1") (pinfunction "1_1") (pintype "passive"))
      (node (ref "R312") (pin "1") (pinfunction "1_1") (pintype "passive"))
      (node (ref "R313") (pin "2") (pinfunction "2_2") (pintype "passive"))
      (node (ref "U301") (pin "IN-") (pinfunction "IN-_IN-") (pintype "bidirectional"))
    )
    (net (code "11") (name "Net-(C307-Pad2)") (class "Default")
      (node (ref "C307") (pin "2") (pinfunction "2_2") (pintype "passive"))
      (node (ref "R313") (pin "1") (pinfunction "1_1") (pintype "passive"))
      (node (ref "R314") (pin "2") (pinfunction "2_2") (pintype "passive"))
      (node (ref "U301") (pin "OUT") (pinfunction "OUT_OUT") (pintype "bidirectional"))
    )
    (net (code "12") (name "Net-(C406-Pad2)") (class "Default")
      (node (ref "C406") (pin "2") (pinfunction "2_2") (pintype "passive"))
      (node (ref "R407") (pin "2") (pinfunction "2_2") (pintype "passive"))
    )
    (net (code "13") (name "Net-(C408-Pad1)") (class "Default")
      (node (ref "C408") (pin "1") (pinfunction "1_1") (pintype "passive"))
      (node (ref "R413") (pin "1") (pinfunction "1_1") (pintype "passive"))
      (node (ref "R414") (pin "2") (pinfunction "2_2") (pintype "passive"))
      (node (ref "U401") (pin "IN+") (pinfunction "IN+_IN+") (pintype "bidirectional"))
    )
    (net (code "14") (name "Net-(C411-Pad1)") (class "Default")
      (node (ref "C411") (pin "1") (pinfunction "1_1") (pintype "passive"))
      (node (ref "R417") (pin "1") (pinfunction "1_1") (pintype "passive"))
      (node (ref "R418") (pin "2") (pinfunction "2_2") (pintype "passive"))
      (node (ref "U401") (pin "IN-") (pinfunction "IN-_IN-") (pintype "bidirectional"))
    )
    (net (code "15") (name "Net-(C411-Pad2)") (class "Default")
      (node (ref "C411") (pin "2") (pinfunction "2_2") (pintype "passive"))
      (node (ref "R418") (pin "1") (pinfunction "1_1") (pintype "passive"))
      (node (ref "R419") (pin "2") (pinfunction "2_2") (pintype "passive"))
      (node (ref "U401") (pin "OUT") (pinfunction "OUT_OUT") (pintype "bidirectional"))
    )
    (net (code "16") (name "Net-(D201-PadA)") (class "Default")
      (node (ref "D201") (pin "A") (pinfunction "A_A") (pintype "passive"))
      (node (ref "R208") (pin "1") (pinfunction "1_1") (pintype "passive"))
    )
    (net (code "17") (name "Net-(D202-PadA)") (class "Default")
      (node (ref "D202") (pin "A") (pinfunction "A_A") (pintype "passive"))
      (node (ref "R209") (pin "1") (pinfunction "1_1") (pintype "passive"))
    )
    (net (code "18") (name "Net-(LED+-PadA)") (class "Default")
      (node (ref "LED+") (pin "A") (pinfunction "A_A") (pintype "passive"))
      (node (ref "R411") (pin "1") (pinfunction "1_1") (pintype "passive"))
    )
    (net (code "19") (name "Net-(LED--PadA)") (class "Default")
      (node (ref "LED-") (pin "A") (pinfunction "A_A") (pintype "passive"))
      (node (ref "R412") (pin "2") (pinfunction "2_2") (pintype "passive"))
    )
    (net (code "20") (name "Net-(LEDU-PadA)") (class "Default")
      (node (ref "LEDU") (pin "A") (pinfunction "A_A") (pintype "passive"))
      (node (ref "R305") (pin "1") (pinfunction "1_1") (pintype "passive"))
    )
    (net (code "21") (name "Net-(LEDV-PadA)") (class "Default")
      (node (ref "LEDV") (pin "A") (pinfunction "A_A") (pintype "passive"))
      (node (ref "R306") (pin "1") (pinfunction "1_1") (pintype "passive"))
    )
    (net (code "22") (name "Net-(LEDW-PadA)") (class "Default")
      (node (ref "LEDW") (pin "A") (pinfunction "A_A") (pintype "passive"))
      (node (ref "R307") (pin "1") (pinfunction "1_1") (pintype "passive"))
    )
    (net (code "23") (name "Net-(U100-PB8-BOOT0)") (class "Default")
      (node (ref "R101") (pin "2") (pinfunction "2_2") (pintype "passive"))
      (node (ref "TP101") (pin "1") (pinfunction "1_1") (pintype "passive"))
      (node (ref "U100") (pin "31") (pinfunction "PB8-BOOT0_31") (pintype "bidirectional"))
    )
    (net (code "24") (name "Net-(U100-PF0-OSC_IN)") (class "Default")
      (node (ref "C105") (pin "1") (pinfunction "1_1") (pintype "passive"))
      (node (ref "U100") (pin "2") (pinfunction "PF0-OSC_IN_2") (pintype "bidirectional"))
      (node (ref "X101") (pin "1") (pinfunction "1_1") (pintype "passive"))
    )
    (net (code "25") (name "Net-(U100-PF1-OSC_OUT)") (class "Default")
      (node (ref "C104") (pin "1") (pinfunction "1_1") (pintype "passive"))
      (node (ref "U100") (pin "3") (pinfunction "PF1-OSC_OUT_3") (pintype "bidirectional"))
      (node (ref "X101") (pin "3") (pinfunction "2_3") (pintype "passive"))
    )
    (net (code "26") (name "Net-(U200-EN)") (class "Default")
      (node (ref "R202") (pin "1") (pinfunction "1_1") (pintype "passive"))
      (node (ref "R203") (pin "2") (pinfunction "2_2") (pintype "passive"))
      (node (ref "TP201") (pin "1") (pinfunction "1_1") (pintype "passive"))
      (node (ref "U200") (pin "1") (pinfunction "PS/SYNC_1") (pintype "input"))
      (node (ref "U200") (pin "14") (pinfunction "EN_14") (pintype "input"))
    )
    (net (code "27") (name "Net-(U200-FB)") (class "Default")
      (node (ref "R205") (pin "1") (pinfunction "1_1") (pintype "passive"))
      (node (ref "R206") (pin "2") (pinfunction "2_2") (pintype "passive"))
      (node (ref "U200") (pin "5") (pinfunction "FB_5") (pintype "passive"))
    )
    (net (code "28") (name "Net-(U200-FB2)") (class "Default")
      (node (ref "TP204") (pin "1") (pinfunction "1_1") (pintype "passive"))
      (node (ref "U200") (pin "6") (pinfunction "FB2_6") (pintype "passive"))
    )
    (net (code "29") (name "Net-(U200-L1)") (class "Default")
      (node (ref "L201") (pin "1") (pinfunction "1_1") (pintype "passive"))
      (node (ref "U200") (pin "11") (pinfunction "L1_11") (pintype "passive"))
    )
    (net (code "30") (name "Net-(U200-L2)") (class "Default")
      (node (ref "L201") (pin "2") (pinfunction "2_2") (pintype "passive"))
      (node (ref "U200") (pin "9") (pinfunction "L2_9") (pintype "passive"))
    )
    (net (code "31") (name "Net-(U200-PG)") (class "Default")
      (node (ref "R207") (pin "1") (pinfunction "1_1") (pintype "passive"))
      (node (ref "TP203") (pin "1") (pinfunction "1_1") (pintype "passive"))
      (node (ref "U200") (pin "2") (pinfunction "PG_2") (pintype "open_collector"))
    )
    (net (code "32") (name "Net-(U200-VAUX)") (class "Default")
      (node (ref "C204") (pin "1") (pinfunction "1_1") (pintype "passive"))
      (node (ref "U200") (pin "3") (pinfunction "VAUX_3") (pintype "output"))
    )
    (net (code "33") (name "Net-(U200-VIN)") (class "Default")
      (node (ref "C201") (pin "1") (pinfunction "1_1") (pintype "passive"))
      (node (ref "C202") (pin "1") (pinfunction "1_1") (pintype "passive"))
      (node (ref "C203") (pin "1") (pinfunction "1_1") (pintype "passive"))
      (node (ref "R201") (pin "1") (pinfunction "1_1") (pintype "passive"))
      (node (ref "R202") (pin "2") (pinfunction "2_2") (pintype "passive"))
      (node (ref "U200") (pin "12-13") (pinfunction "VIN_12-13") (pintype "power_in"))
    )
    (net (code "34") (name "Net-(U200-VSEL)") (class "Default")
      (node (ref "R204") (pin "2") (pinfunction "2_2") (pintype "passive"))
      (node (ref "TP202") (pin "1") (pinfunction "1_1") (pintype "passive"))
      (node (ref "U200") (pin "15") (pinfunction "VSEL_15") (pintype "input"))
    )
    (net (code "35") (name "Net-(U300-OUTU)") (class "Default")
      (node (ref "JP301") (pin "1") (pinfunction "1_1") (pintype "passive"))
      (node (ref "R305") (pin "2") (pinfunction "2_2") (pintype "passive"))
      (node (ref "U300") (pin "3") (pinfunction "OUTU_3") (pintype "output"))
    )
    (net (code "36") (name "Net-(U300-OUTV)") (class "Default")
      (node (ref "JP301") (pin "2") (pinfunction "2_2") (pintype "passive"))
      (node (ref "R306") (pin "2") (pinfunction "2_2") (pintype "passive"))
      (node (ref "U300") (pin "8") (pinfunction "OUTV_8") (pintype "output"))
    )
    (net (code "37") (name "Net-(U300-OUTW)") (class "Default")
      (node (ref "JP301") (pin "3") (pinfunction "3_3") (pintype "passive"))
      (node (ref "R307") (pin "2") (pinfunction "2_2") (pintype "passive"))
      (node (ref "U300") (pin "10") (pinfunction "OUTW_10") (pintype "output"))
    )
    (net (code "38") (name "Net-(U300-SENSEU)") (class "Default")
      (node (ref "R309") (pin "1") (pinfunction "1_1") (pintype "passive"))
      (node (ref "R310") (pin "2") (pinfunction "2_2") (pintype "passive"))
      (node (ref "R311") (pin "2") (pinfunction "2_2") (pintype "passive"))
      (node (ref "U300") (pin "4") (pinfunction "SENSEU_4") (pintype "output"))
      (node (ref "U300") (pin "9") (pinfunction "SENSEVW_9") (pintype "output"))
    )
    (net (code "39") (name "Net-(U300-VS)") (class "Default")
      (node (ref "C301") (pin "1") (pinfunction "1_1") (pintype "passive"))
      (node (ref "C302") (pin "1") (pinfunction "1_1") (pintype "passive"))
      (node (ref "C303") (pin "1") (pinfunction "1_1") (pintype "passive"))
      (node (ref "R303") (pin "1") (pinfunction "1_1") (pintype "passive"))
      (node (ref "R304") (pin "1") (pinfunction "1_1") (pintype "passive"))
      (node (ref "U300") (pin "6") (pinfunction "VS_6") (pintype "power_in"))
    )
    (net (code "40") (name "Net-(U302-A)") (class "Default")
      (node (ref "JP302") (pin "2") (pinfunction "2_2") (pintype "passive"))
      (node (ref "U302") (pin "7") (pinfunction "A_7") (pintype "output"))
    )
    (net (code "41") (name "Net-(U302-B)") (class "Default")
      (node (ref "JP302") (pin "1") (pinfunction "1_1") (pintype "passive"))
      (node (ref "U302") (pin "6") (pinfunction "B_6") (pintype "output"))
    )
    (net (code "42") (name "Net-(U302-MOSI)") (class "Default")
      (node (ref "R315") (pin "2") (pinfunction "2_2") (pintype "passive"))
      (node (ref "U302") (pin "4") (pinfunction "MOSI_4") (pintype "input"))
    )
    (net (code "43") (name "Net-(U400-OUTA1)") (class "Default")
      (node (ref "JP401") (pin "1") (pinfunction "1_1") (pintype "passive"))
      (node (ref "R411") (pin "2") (pinfunction "2_2") (pintype "passive"))
      (node (ref "U400") (pin "10") (pinfunction "OUTB1_10") (pintype "output"))
      (node (ref "U400") (pin "3") (pinfunction "OUTA1_3") (pintype "output"))
    )
    (net (code "44") (name "Net-(U400-OUTA2)") (class "Default")
      (node (ref "JP401") (pin "2") (pinfunction "2_2") (pintype "passive"))
      (node (ref "R412") (pin "1") (pinfunction "1_1") (pintype "passive"))
      (node (ref "U400") (pin "5") (pinfunction "OUTA2_5") (pintype "output"))
      (node (ref "U400") (pin "8") (pinfunction "OUTB2_8") (pintype "output"))
    )
    (net (code "45") (name "Net-(U400-PH)") (class "Default")
      (node (ref "R405") (pin "1") (pinfunction "1_1") (pintype "passive"))
      (node (ref "U400") (pin "1") (pinfunction "PH_1") (pintype "input"))
    )
    (net (code "46") (name "Net-(U400-PWM)") (class "Default")
      (node (ref "R406") (pin "1") (pinfunction "1_1") (pintype "passive"))
      (node (ref "U400") (pin "2") (pinfunction "PWM_2") (pintype "input"))
    )
    (net (code "47") (name "Net-(U400-REF)") (class "Default")
      (node (ref "C407") (pin "2") (pinfunction "2_2") (pintype "passive"))
      (node (ref "R409") (pin "2") (pinfunction "2_2") (pintype "passive"))
      (node (ref "R410") (pin "1") (pinfunction "1_1") (pintype "passive"))
      (node (ref "U400") (pin "11") (pinfunction "REF_11") (pintype "passive"))
    )
    (net (code "48") (name "Net-(U400-SENSEA)") (class "Default")
      (node (ref "R414") (pin "1") (pinfunction "1_1") (pintype "passive"))
      (node (ref "R415") (pin "1") (pinfunction "1_1") (pintype "passive"))
      (node (ref "R416") (pin "1") (pinfunction "1_1") (pintype "passive"))
      (node (ref "U400") (pin "4") (pinfunction "SENSEA_4") (pintype "output"))
      (node (ref "U400") (pin "9") (pinfunction "SENSEB_9") (pintype "output"))
    )
    (net (code "49") (name "Net-(U400-TOFF)") (class "Default")
      (node (ref "R407") (pin "1") (pinfunction "1_1") (pintype "passive"))
      (node (ref "R408") (pin "1") (pinfunction "1_1") (pintype "passive"))
      (node (ref "U400") (pin "12") (pinfunction "TOFF_12") (pintype "passive"))
    )
    (net (code "50") (name "Net-(U400-VS)") (class "Default")
      (node (ref "C401") (pin "1") (pinfunction "1_1") (pintype "passive"))
      (node (ref "C402") (pin "1") (pinfunction "1_1") (pintype "passive"))
      (node (ref "C403") (pin "1") (pinfunction "1_1") (pintype "passive"))
      (node (ref "R403") (pin "1") (pinfunction "1_1") (pintype "passive"))
      (node (ref "R404") (pin "1") (pinfunction "1_1") (pintype "passive"))
      (node (ref "U400") (pin "6") (pinfunction "VS_6") (pintype "power_in"))
    )
    (net (code "51") (name "PA0{slash}CURR_FDB_MAG") (class "Default")
      (node (ref "R419") (pin "1") (pinfunction "1_1") (pintype "passive"))
      (node (ref "TP1") (pin "1") (pinfunction "1_1") (pintype "passive"))
      (node (ref "U100") (pin "6") (pinfunction "PA0_6") (pintype "bidirectional"))
    )
    (net (code "52") (name "PA1{slash}CURR_FDB_BLDC") (class "Default")
      (node (ref "R314") (pin "1") (pinfunction "1_1") (pintype "passive"))
      (node (ref "TP2") (pin "1") (pinfunction "1_1") (pintype "passive"))
      (node (ref "U100") (pin "7") (pinfunction "PA1_7") (pintype "bidirectional"))
    )
    (net (code "53") (name "PA2{slash}USART2_TX") (class "Default")
      (node (ref "JP102") (pin "P$2") (pinfunction "TXO_P$2") (pintype "passive"))
      (node (ref "U100") (pin "8") (pinfunction "PA2_8") (pintype "bidirectional"))
    )
    (net (code "54") (name "PA3{slash}USART2_RX") (class "Default")
      (node (ref "JP102") (pin "P$3") (pinfunction "RXI_P$3") (pintype "passive"))
      (node (ref "U100") (pin "9") (pinfunction "PA3_9") (pintype "bidirectional"))
    )
    (net (code "55") (name "PA4{slash}FAULT_BLDC") (class "Default")
      (node (ref "C305") (pin "2") (pinfunction "2_2") (pintype "passive"))
      (node (ref "R302") (pin "1") (pinfunction "1_1") (pintype "passive"))
      (node (ref "U100") (pin "10") (pinfunction "PA4_10") (pintype "bidirectional"))
      (node (ref "U300") (pin "13") (pinfunction "EN/FAULT_13") (pintype "bidirectional"))
    )
    (net (code "56") (name "PA5{slash}SPI1_SCK") (class "Default")
      (node (ref "U100") (pin "11") (pinfunction "PA5_11") (pintype "bidirectional"))
      (node (ref "U302") (pin "2") (pinfunction "SCLK_2") (pintype "input"))
    )
    (net (code "57") (name "PA6{slash}CAN_LSTN") (class "Default")
      (node (ref "U100") (pin "12") (pinfunction "PA6_12") (pintype "bidirectional"))
      (node (ref "U101") (pin "8") (pinfunction "S_8") (pintype "input"))
    )
    (net (code "58") (name "PA7{slash}INUL") (class "Default")
      (node (ref "TP3") (pin "1") (pinfunction "1_1") (pintype "passive"))
      (node (ref "U100") (pin "13") (pinfunction "PA7_13") (pintype "bidirectional"))
      (node (ref "U300") (pin "1") (pinfunction "INUL_1") (pintype "input"))
    )
    (net (code "59") (name "PA8{slash}INUH{slash}PWM_MAG") (class "Default")
      (node (ref "R406") (pin "2") (pinfunction "2_2") (pintype "passive"))
      (node (ref "TP4") (pin "1") (pinfunction "1_1") (pintype "passive"))
      (node (ref "U100") (pin "18") (pinfunction "PA8_18") (pintype "bidirectional"))
      (node (ref "U300") (pin "2") (pinfunction "INUH_2") (pintype "input"))
    )
    (net (code "60") (name "PA9{slash}INVH{slash}DIR_MAG") (class "Default")
      (node (ref "R405") (pin "2") (pinfunction "2_2") (pintype "passive"))
      (node (ref "TP5") (pin "1") (pinfunction "1_1") (pintype "passive"))
      (node (ref "U100") (pin "19") (pinfunction "PA9_19") (pintype "bidirectional"))
      (node (ref "U300") (pin "16") (pinfunction "INVH_16") (pintype "input"))
    )
    (net (code "61") (name "PA10{slash}INWH") (class "Default")
      (node (ref "TP6") (pin "1") (pinfunction "1_1") (pintype "passive"))
      (node (ref "U100") (pin "20") (pinfunction "PA10_20") (pintype "bidirectional"))
      (node (ref "U300") (pin "12") (pinfunction "INWH_12") (pintype "input"))
    )
    (net (code "62") (name "PA15{slash}SPI1_NSS") (class "Default")
      (node (ref "U100") (pin "25") (pinfunction "PA15_25") (pintype "bidirectional"))
      (node (ref "U302") (pin "1") (pinfunction "CSN_1") (pintype "input"))
    )
    (net (code "63") (name "PB0{slash}INVL") (class "Default")
      (node (ref "TP7") (pin "1") (pinfunction "1_1") (pintype "passive"))
      (node (ref "U100") (pin "14") (pinfunction "PB0_14") (pintype "bidirectional"))
      (node (ref "U300") (pin "15") (pinfunction "INVL_15") (pintype "input"))
    )
    (net (code "64") (name "PB1{slash}INWL") (class "Default")
      (node (ref "TP8") (pin "1") (pinfunction "1_1") (pintype "passive"))
      (node (ref "U100") (pin "15") (pinfunction "PB1_15") (pintype "bidirectional"))
      (node (ref "U300") (pin "11") (pinfunction "INWL_11") (pintype "input"))
    )
    (net (code "65") (name "PB3{slash}EN_MAG") (class "Default")
      (node (ref "R402") (pin "2") (pinfunction "2_2") (pintype "passive"))
      (node (ref "U100") (pin "26") (pinfunction "PB3_26") (pintype "bidirectional"))
    )
    (net (code "66") (name "PB4{slash}SPI1_MISO") (class "Default")
      (node (ref "U100") (pin "27") (pinfunction "PB4_27") (pintype "bidirectional"))
      (node (ref "U302") (pin "3") (pinfunction "MISO_3") (pintype "output"))
    )
    (net (code "67") (name "PB5") (class "Default")
      (node (ref "U100") (pin "28") (pinfunction "PB5_28") (pintype "bidirectional"))
    )
    (net (code "68") (name "PB6{slash}EN_BLDC") (class "Default")
      (node (ref "R302") (pin "2") (pinfunction "2_2") (pintype "passive"))
      (node (ref "U100") (pin "29") (pinfunction "PB6_29") (pintype "bidirectional"))
    )
    (net (code "69") (name "PB7{slash}FAULT_MAG") (class "Default")
      (node (ref "C405") (pin "2") (pinfunction "2_2") (pintype "passive"))
      (node (ref "R402") (pin "1") (pinfunction "1_1") (pintype "passive"))
      (node (ref "U100") (pin "30") (pinfunction "PB7_30") (pintype "bidirectional"))
      (node (ref "U400") (pin "13") (pinfunction "EN/FAULT_13") (pintype "bidirectional"))
    )
    (net (code "70") (name "STBY{slash}RESET_BLDC") (class "Default")
      (node (ref "C304") (pin "2") (pinfunction "2_2") (pintype "passive"))
      (node (ref "R301") (pin "1") (pinfunction "1_1") (pintype "passive"))
      (node (ref "TP9") (pin "TP") (pinfunction "TP_TP") (pintype "input"))
      (node (ref "U300") (pin "14") (pinfunction "STBY/RESET_14") (pintype "input"))
    )
    (net (code "71") (name "STBY{slash}RESET_MAG") (class "Default")
      (node (ref "C404") (pin "2") (pinfunction "2_2") (pintype "passive"))
      (node (ref "R401") (pin "1") (pinfunction "1_1") (pintype "passive"))
      (node (ref "TP10") (pin "TP") (pinfunction "TP_TP") (pintype "input"))
      (node (ref "U400") (pin "14") (pinfunction "STBY/RESET_14") (pintype "bidirectional"))
    )
    (net (code "72") (name "SWCLK") (class "Default")
      (node (ref "J1") (pin "SWDCLK") (pinfunction "SWDCLK/TCK_SWDCLK") (pintype "passive"))
      (node (ref "U100") (pin "24") (pinfunction "PA14-SWCLK_24") (pintype "bidirectional"))
    )
    (net (code "73") (name "SWDIO") (class "Default")
      (node (ref "J1") (pin "SWDIO") (pinfunction "SWDIO/TMS_SWDIO") (pintype "passive"))
      (node (ref "U100") (pin "23") (pinfunction "PA13-SWDIO_23") (pintype "bidirectional"))
    )
    (net (code "74") (name "V_BATT") (class "Default")
      (node (ref "JP101") (pin "1") (pinfunction "1_1") (pintype "passive"))
      (node (ref "R201") (pin "2") (pinfunction "2_2") (pintype "passive"))
      (node (ref "R208") (pin "2") (pinfunction "2_2") (pintype "passive"))
      (node (ref "R303") (pin "2") (pinfunction "2_2") (pintype "passive"))
      (node (ref "R403") (pin "2") (pinfunction "2_2") (pintype "passive"))
    )
    (net (code "75") (name "unconnected-(J1-NC{slash}TDI-PadNC)") (class "Default")
      (node (ref "J1") (pin "NC") (pinfunction "NC/TDI_NC") (pintype "passive"))
    )
    (net (code "76") (name "unconnected-(J1-PadGNDDET)") (class "Default")
      (node (ref "J1") (pin "GNDDET") (pinfunction "GNDDET_GNDDET") (pintype "passive"))
    )
    (net (code "77") (name "unconnected-(J1-SWO{slash}TDO-PadSWO)") (class "Default")
      (node (ref "J1") (pin "SWO") (pinfunction "SWO/TDO_SWO") (pintype "passive"))
    )
    (net (code "78") (name "unconnected-(JP102-CTS-PadP$5)") (class "Default")
      (node (ref "JP102") (pin "P$5") (pinfunction "CTS_P$5") (pintype "passive"))
    )
    (net (code "79") (name "unconnected-(JP102-DTR-PadP$1)") (class "Default")
      (node (ref "JP102") (pin "P$1") (pinfunction "DTR_P$1") (pintype "passive"))
    )
    (net (code "80") (name "unconnected-(JP102-VCC-PadP$4)") (class "Default")
      (node (ref "JP102") (pin "P$4") (pinfunction "VCC_P$4") (pintype "passive"))
    )
    (net (code "81") (name "unconnected-(U302-I{slash}PWM-Pad14)") (class "Default")
      (node (ref "U302") (pin "14") (pinfunction "I/PWM_14") (pintype "output"))
    )
    (net (code "82") (name "unconnected-(U302-U-Pad10)") (class "Default")
      (node (ref "U302") (pin "10") (pinfunction "U_10") (pintype "output"))
    )
    (net (code "83") (name "unconnected-(U302-V-Pad9)") (class "Default")
      (node (ref "U302") (pin "9") (pinfunction "V_9") (pintype "output"))
    )
    (net (code "84") (name "unconnected-(U302-W{slash}PWM-Pad8)") (class "Default")
      (node (ref "U302") (pin "8") (pinfunction "W/PWM_8") (pintype "output"))
    )
  )
)
